# OK1050-C_V1_2_Audio.net
KiCad netlist of a schematic drawn in Altium Designer
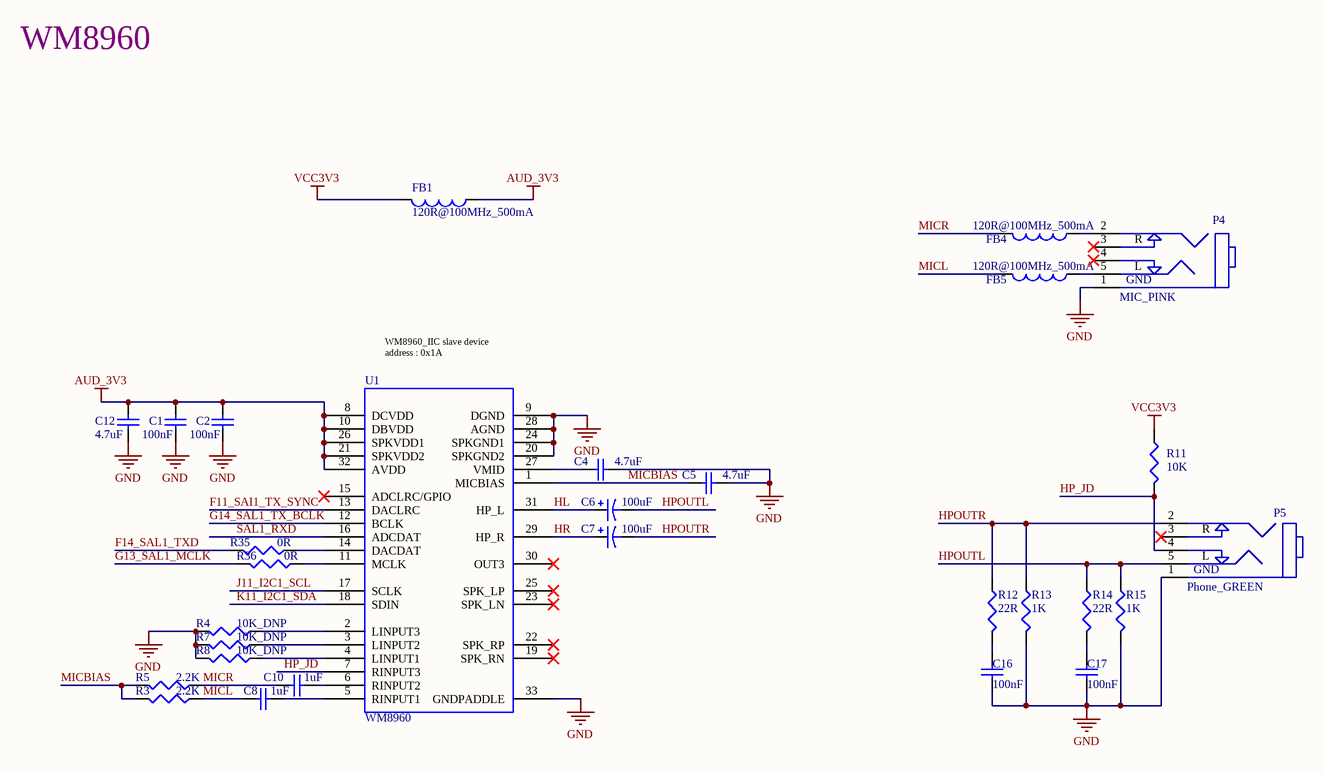
[diagram p0: OK1050-C_V1.2_Audio.SchDoc]

(export (version "E")
  (design (tool "Eeschema 10.0.6"))
  (components
    (comp (ref "C1")
      (value "100nF")
      (footprint "0603C+")
      (description "Capacitor")
      (fields (field (name "PUBLISHER") "Altium Limited"))
      (libsource (lib "Miscellaneous Devices") (part "Cap"))
    )
    (comp (ref "C2")
      (value "100nF")
      (footprint "0603C+")
      (description "Capacitor")
      (fields (field (name "PUBLISHER") "Altium Limited"))
      (libsource (lib "Miscellaneous Devices") (part "Cap"))
    )
    (comp (ref "C4")
      (value "4.7uF")
      (footprint "0603C+")
      (description "Capacitor")
      (fields (field (name "PUBLISHER") "Altium Limited"))
      (libsource (lib "Miscellaneous Devices") (part "Cap"))
    )
    (comp (ref "C5")
      (value "4.7uF")
      (footprint "0603C+")
      (description "Capacitor")
      (fields (field (name "PUBLISHER") "Altium Limited"))
      (libsource (lib "Miscellaneous Devices") (part "Cap"))
    )
    (comp (ref "C6")
      (value "100uF")
      (footprint "TC3528B")
      (description "Polarized Capacitor (Radial)")
      (fields (field (name "PUBLISHER") "Altium Limited"))
      (libsource (lib "Miscellaneous Devices") (part "Cap Pol1"))
    )
    (comp (ref "C7")
      (value "100uF")
      (footprint "TC3528B")
      (description "Polarized Capacitor (Radial)")
      (fields (field (name "PUBLISHER") "Altium Limited"))
      (libsource (lib "Miscellaneous Devices") (part "Cap Pol1"))
    )
    (comp (ref "C8")
      (value "1uF")
      (footprint "0603C+")
      (description "Capacitor")
      (fields (field (name "PUBLISHER") "Altium Limited"))
      (libsource (lib "Miscellaneous Devices") (part "Cap"))
    )
    (comp (ref "C10")
      (value "1uF")
      (footprint "0603C+")
      (description "Capacitor")
      (fields (field (name "PUBLISHER") "Altium Limited"))
      (libsource (lib "Miscellaneous Devices") (part "Cap"))
    )
    (comp (ref "C12")
      (value "4.7uF")
      (footprint "0603C+")
      (description "Capacitor")
      (fields (field (name "PUBLISHER") "Altium Limited"))
      (libsource (lib "Miscellaneous Devices") (part "Cap"))
    )
    (comp (ref "C16")
      (value "100nF")
      (footprint "0603C+")
      (description "Capacitor")
      (fields (field (name "PUBLISHER") "Altium Limited"))
      (libsource (lib "Miscellaneous Devices") (part "Cap"))
    )
    (comp (ref "C17")
      (value "100nF")
      (footprint "0603C+")
      (description "Capacitor")
      (fields (field (name "PUBLISHER") "Altium Limited"))
      (libsource (lib "Miscellaneous Devices") (part "Cap"))
    )
    (comp (ref "FB1")
      (value "120R@100MHz_500mA")
      (footprint "0603R+")
      (description "Inductor")
      (fields (field (name "PUBLISHER") "Altium Limited"))
      (libsource (lib "Miscellaneous Devices") (part "Inductor"))
    )
    (comp (ref "FB4")
      (value "120R@100MHz_500mA")
      (footprint "0603R+")
      (description "Inductor")
      (fields (field (name "PUBLISHER") "Altium Limited"))
      (libsource (lib "Miscellaneous Devices") (part "Inductor"))
    )
    (comp (ref "FB5")
      (value "120R@100MHz_500mA")
      (footprint "0603R+")
      (description "Inductor")
      (fields (field (name "PUBLISHER") "Altium Limited"))
      (libsource (lib "Miscellaneous Devices") (part "Inductor"))
    )
    (comp (ref "P4")
      (value "MIC_PINK")
      (footprint "PHONEJACK SW")
      (libsource (lib "Miscellaneous Devices") (part "Phonejack Stereo SW"))
    )
    (comp (ref "P5")
      (value "Phone_GREEN")
      (footprint "PHONEJACK SW")
      (libsource (lib "IMX6QP-C") (part "Phonejack Stereo SW"))
    )
    (comp (ref "R3")
      (value "2.2K")
      (footprint "0603R+")
      (description "Resistor")
      (fields (field (name "PUBLISHER") "Altium Limited"))
      (libsource (lib "Miscellaneous Devices") (part "Res3"))
    )
    (comp (ref "R4")
      (value "10K_DNP")
      (footprint "0603R+")
      (description "Resistor")
      (fields (field (name "PUBLISHER") "Altium Limited"))
      (libsource (lib "Miscellaneous Devices") (part "Res3"))
    )
    (comp (ref "R5")
      (value "2.2K")
      (footprint "0603R+")
      (description "Resistor")
      (fields (field (name "PUBLISHER") "Altium Limited"))
      (libsource (lib "Miscellaneous Devices") (part "Res3"))
    )
    (comp (ref "R7")
      (value "10K_DNP")
      (footprint "0603R+")
      (description "Resistor")
      (fields (field (name "PUBLISHER") "Altium Limited"))
      (libsource (lib "Miscellaneous Devices") (part "Res3"))
    )
    (comp (ref "R8")
      (value "10K_DNP")
      (footprint "0603R+")
      (description "Resistor")
      (fields (field (name "PUBLISHER") "Altium Limited"))
      (libsource (lib "Miscellaneous Devices") (part "Res3"))
    )
    (comp (ref "R11")
      (value "10K")
      (footprint "0603R+")
      (description "Resistor")
      (fields (field (name "PUBLISHER") "Altium Limited"))
      (libsource (lib "Miscellaneous Devices") (part "Res3"))
    )
    (comp (ref "R12")
      (value "22R")
      (footprint "0603R+")
      (description "Resistor")
      (fields (field (name "PUBLISHER") "Altium Limited"))
      (libsource (lib "Miscellaneous Devices") (part "Res3"))
    )
    (comp (ref "R13")
      (value "1K")
      (footprint "0603R+")
      (description "Resistor")
      (fields (field (name "PUBLISHER") "Altium Limited"))
      (libsource (lib "Miscellaneous Devices") (part "Res3"))
    )
    (comp (ref "R14")
      (value "22R")
      (footprint "0603R+")
      (description "Resistor")
      (fields (field (name "PUBLISHER") "Altium Limited"))
      (libsource (lib "Miscellaneous Devices") (part "Res3"))
    )
    (comp (ref "R15")
      (value "1K")
      (footprint "0603R+")
      (description "Resistor")
      (fields (field (name "PUBLISHER") "Altium Limited"))
      (libsource (lib "Miscellaneous Devices") (part "Res3"))
    )
    (comp (ref "R35")
      (value "0R")
      (footprint "0603R+")
      (description "Resistor")
      (fields (field (name "PUBLISHER") "Altium Limited"))
      (libsource (lib "Miscellaneous Devices") (part "Res3"))
    )
    (comp (ref "R36")
      (value "0R")
      (footprint "0603R+")
      (description "Resistor")
      (fields (field (name "PUBLISHER") "Altium Limited"))
      (libsource (lib "Miscellaneous Devices") (part "Res3"))
    )
    (comp (ref "U1") (value "WM8960") (footprint "WM8960") (libsource (lib "IMX6QP-C") (part "WM8960")))
  )
  (nets
    (net (code "1") (name "/F11_SAI1_TX_SYNC") (class "Default")
      (node (ref "U1") (pin "13") (pinfunction "DACLRC_13") (pintype "passive"))
    )
    (net (code "2") (name "/F14_SAL1_TXD") (class "Default")
      (node (ref "R35") (pin "2") (pinfunction "2_2") (pintype "passive"))
    )
    (net (code "3") (name "/G13_SAL1_MCLK") (class "Default")
      (node (ref "R36") (pin "2") (pinfunction "2_2") (pintype "passive"))
    )
    (net (code "4") (name "/G14_SAL1_TX_BCLK") (class "Default")
      (node (ref "U1") (pin "12") (pinfunction "BCLK_12") (pintype "passive"))
    )
    (net (code "5") (name "/HL") (class "Default")
      (node (ref "C6") (pin "1") (pinfunction "1_1") (pintype "passive"))
      (node (ref "U1") (pin "31") (pinfunction "HP_L_31") (pintype "passive"))
    )
    (net (code "6") (name "/HPOUTL") (class "Default")
      (node (ref "C6") (pin "2") (pinfunction "2_2") (pintype "passive"))
      (node (ref "P5") (pin "5") (pinfunction "5_5") (pintype "passive"))
      (node (ref "R14") (pin "1") (pinfunction "1_1") (pintype "passive"))
      (node (ref "R15") (pin "1") (pinfunction "1_1") (pintype "passive"))
    )
    (net (code "7") (name "/HPOUTR") (class "Default")
      (node (ref "C7") (pin "2") (pinfunction "2_2") (pintype "passive"))
      (node (ref "P5") (pin "2") (pinfunction "2_2") (pintype "passive"))
      (node (ref "R12") (pin "1") (pinfunction "1_1") (pintype "passive"))
      (node (ref "R13") (pin "1") (pinfunction "1_1") (pintype "passive"))
    )
    (net (code "8") (name "/HP_JD") (class "Default")
      (node (ref "P5") (pin "4") (pinfunction "4_4") (pintype "passive"))
      (node (ref "R11") (pin "2") (pinfunction "2_2") (pintype "passive"))
      (node (ref "U1") (pin "7") (pinfunction "RINPUT3_7") (pintype "passive"))
    )
    (net (code "9") (name "/HR") (class "Default")
      (node (ref "C7") (pin "1") (pinfunction "1_1") (pintype "passive"))
      (node (ref "U1") (pin "29") (pinfunction "HP_R_29") (pintype "passive"))
    )
    (net (code "10") (name "/J11_I2C1_SCL") (class "Default")
      (node (ref "U1") (pin "17") (pinfunction "SCLK_17") (pintype "passive"))
    )
    (net (code "11") (name "/K11_I2C1_SDA") (class "Default")
      (node (ref "U1") (pin "18") (pinfunction "SDIN_18") (pintype "passive"))
    )
    (net (code "12") (name "/MICBIAS") (class "Default")
      (node (ref "C5") (pin "2") (pinfunction "2_2") (pintype "passive"))
      (node (ref "R3") (pin "2") (pinfunction "2_2") (pintype "passive"))
      (node (ref "R5") (pin "2") (pinfunction "2_2") (pintype "passive"))
      (node (ref "U1") (pin "1") (pinfunction "MICBIAS_1") (pintype "passive"))
    )
    (net (code "13") (name "/MICL") (class "Default")
      (node (ref "C8") (pin "2") (pinfunction "2_2") (pintype "passive"))
      (node (ref "FB5") (pin "2") (pinfunction "2_2") (pintype "passive"))
      (node (ref "R3") (pin "1") (pinfunction "1_1") (pintype "passive"))
    )
    (net (code "14") (name "/MICR") (class "Default")
      (node (ref "C10") (pin "2") (pinfunction "2_2") (pintype "passive"))
      (node (ref "FB4") (pin "2") (pinfunction "2_2") (pintype "passive"))
      (node (ref "R5") (pin "1") (pinfunction "1_1") (pintype "passive"))
    )
    (net (code "15") (name "/SAL1_RXD") (class "Default")
      (node (ref "U1") (pin "16") (pinfunction "ADCDAT_16") (pintype "passive"))
    )
    (net (code "16") (name "AUD_3V3") (class "Default")
      (node (ref "C1") (pin "2") (pinfunction "2_2") (pintype "passive"))
      (node (ref "C12") (pin "2") (pinfunction "2_2") (pintype "passive"))
      (node (ref "C2") (pin "2") (pinfunction "2_2") (pintype "passive"))
      (node (ref "FB1") (pin "1") (pinfunction "1_1") (pintype "passive"))
      (node (ref "U1") (pin "10") (pinfunction "DBVDD_10") (pintype "passive"))
      (node (ref "U1") (pin "21") (pinfunction "SPKVDD2_21") (pintype "passive"))
      (node (ref "U1") (pin "26") (pinfunction "SPKVDD1_26") (pintype "passive"))
      (node (ref "U1") (pin "32") (pinfunction "AVDD_32") (pintype "passive"))
      (node (ref "U1") (pin "8") (pinfunction "DCVDD_8") (pintype "passive"))
    )
    (net (code "17") (name "GND") (class "Default")
      (node (ref "C1") (pin "1") (pinfunction "1_1") (pintype "passive"))
      (node (ref "C12") (pin "1") (pinfunction "1_1") (pintype "passive"))
      (node (ref "C16") (pin "2") (pinfunction "2_2") (pintype "passive"))
      (node (ref "C17") (pin "2") (pinfunction "2_2") (pintype "passive"))
      (node (ref "C2") (pin "1") (pinfunction "1_1") (pintype "passive"))
      (node (ref "C4") (pin "1") (pinfunction "1_1") (pintype "passive"))
      (node (ref "C5") (pin "1") (pinfunction "1_1") (pintype "passive"))
      (node (ref "P4") (pin "1") (pinfunction "GND_1") (pintype "passive"))
      (node (ref "P5") (pin "1") (pinfunction "GND_1") (pintype "passive"))
      (node (ref "R13") (pin "2") (pinfunction "2_2") (pintype "passive"))
      (node (ref "R15") (pin "2") (pinfunction "2_2") (pintype "passive"))
      (node (ref "R4") (pin "2") (pinfunction "2_2") (pintype "passive"))
      (node (ref "R7") (pin "2") (pinfunction "2_2") (pintype "passive"))
      (node (ref "R8") (pin "2") (pinfunction "2_2") (pintype "passive"))
      (node (ref "U1") (pin "20") (pinfunction "SPKGND2_20") (pintype "passive"))
      (node (ref "U1") (pin "24") (pinfunction "SPKGND1_24") (pintype "passive"))
      (node (ref "U1") (pin "28") (pinfunction "AGND_28") (pintype "passive"))
      (node (ref "U1") (pin "33") (pinfunction "GNDPADDLE_33") (pintype "passive"))
      (node (ref "U1") (pin "9") (pinfunction "DGND_9") (pintype "passive"))
    )
    (net (code "18") (name "Net-(C16-Pad1)") (class "Default")
      (node (ref "C16") (pin "1") (pinfunction "1_1") (pintype "passive"))
      (node (ref "R12") (pin "2") (pinfunction "2_2") (pintype "passive"))
    )
    (net (code "19") (name "Net-(C17-Pad1)") (class "Default")
      (node (ref "C17") (pin "1") (pinfunction "1_1") (pintype "passive"))
      (node (ref "R14") (pin "2") (pinfunction "2_2") (pintype "passive"))
    )
    (net (code "20") (name "Net-(FB4-Pad1)") (class "Default")
      (node (ref "FB4") (pin "1") (pinfunction "1_1") (pintype "passive"))
      (node (ref "P4") (pin "2") (pinfunction "2_2") (pintype "passive"))
    )
    (net (code "21") (name "Net-(FB5-Pad1)") (class "Default")
      (node (ref "FB5") (pin "1") (pinfunction "1_1") (pintype "passive"))
      (node (ref "P4") (pin "5") (pinfunction "5_5") (pintype "passive"))
    )
    (net (code "22") (name "Net-(U1-DACDAT)") (class "Default")
      (node (ref "R35") (pin "1") (pinfunction "1_1") (pintype "passive"))
      (node (ref "U1") (pin "14") (pinfunction "DACDAT_14") (pintype "passive"))
    )
    (net (code "23") (name "Net-(U1-LINPUT1)") (class "Default")
      (node (ref "R8") (pin "1") (pinfunction "1_1") (pintype "passive"))
      (node (ref "U1") (pin "4") (pinfunction "LINPUT1_4") (pintype "passive"))
    )
    (net (code "24") (name "Net-(U1-LINPUT2)") (class "Default")
      (node (ref "R7") (pin "1") (pinfunction "1_1") (pintype "passive"))
      (node (ref "U1") (pin "3") (pinfunction "LINPUT2_3") (pintype "passive"))
    )
    (net (code "25") (name "Net-(U1-LINPUT3)") (class "Default")
      (node (ref "R4") (pin "1") (pinfunction "1_1") (pintype "passive"))
      (node (ref "U1") (pin "2") (pinfunction "LINPUT3_2") (pintype "passive"))
    )
    (net (code "26") (name "Net-(U1-MCLK)") (class "Default")
      (node (ref "R36") (pin "1") (pinfunction "1_1") (pintype "passive"))
      (node (ref "U1") (pin "11") (pinfunction "MCLK_11") (pintype "passive"))
    )
    (net (code "27") (name "Net-(U1-RINPUT1)") (class "Default")
      (node (ref "C8") (pin "1") (pinfunction "1_1") (pintype "passive"))
      (node (ref "U1") (pin "5") (pinfunction "RINPUT1_5") (pintype "passive"))
    )
    (net (code "28") (name "Net-(U1-RINPUT2)") (class "Default")
      (node (ref "C10") (pin "1") (pinfunction "1_1") (pintype "passive"))
      (node (ref "U1") (pin "6") (pinfunction "RINPUT2_6") (pintype "passive"))
    )
    (net (code "29") (name "Net-(U1-VMID)") (class "Default")
      (node (ref "C4") (pin "2") (pinfunction "2_2") (pintype "passive"))
      (node (ref "U1") (pin "27") (pinfunction "VMID_27") (pintype "passive"))
    )
    (net (code "30") (name "VCC3V3") (class "Default")
      (node (ref "FB1") (pin "2") (pinfunction "2_2") (pintype "passive"))
      (node (ref "R11") (pin "1") (pinfunction "1_1") (pintype "passive"))
    )
    (net (code "31") (name "unconnected-(P4-Pad3)") (class "Default")
      (node (ref "P4") (pin "3") (pinfunction "3_3") (pintype "passive+no_connect"))
    )
    (net (code "32") (name "unconnected-(P4-Pad4)") (class "Default")
      (node (ref "P4") (pin "4") (pinfunction "4_4") (pintype "passive+no_connect"))
    )
    (net (code "33") (name "unconnected-(P5-Pad3)") (class "Default")
      (node (ref "P5") (pin "3") (pinfunction "3_3") (pintype "passive+no_connect"))
    )
    (net (code "34") (name "unconnected-(U1-ADCLRC{slash}GPIO-Pad15)") (class "Default")
      (node (ref "U1") (pin "15") (pinfunction "ADCLRC/GPIO_15") (pintype "passive+no_connect"))
    )
    (net (code "35") (name "unconnected-(U1-OUT3-Pad30)") (class "Default")
      (node (ref "U1") (pin "30") (pinfunction "OUT3_30") (pintype "passive+no_connect"))
    )
    (net (code "36") (name "unconnected-(U1-SPK_LN-Pad23)") (class "Default")
      (node (ref "U1") (pin "23") (pinfunction "SPK_LN_23") (pintype "passive+no_connect"))
    )
    (net (code "37") (name "unconnected-(U1-SPK_LP-Pad25)") (class "Default")
      (node (ref "U1") (pin "25") (pinfunction "SPK_LP_25") (pintype "passive+no_connect"))
    )
    (net (code "38") (name "unconnected-(U1-SPK_RN-Pad19)") (class "Default")
      (node (ref "U1") (pin "19") (pinfunction "SPK_RN_19") (pintype "passive+no_connect"))
    )
    (net (code "39") (name "unconnected-(U1-SPK_RP-Pad22)") (class "Default")
      (node (ref "U1") (pin "22") (pinfunction "SPK_RP_22") (pintype "passive+no_connect"))
    )
  )
)
